# 12v-switch.net
KiCad netlist of a schematic drawn in EAGLE
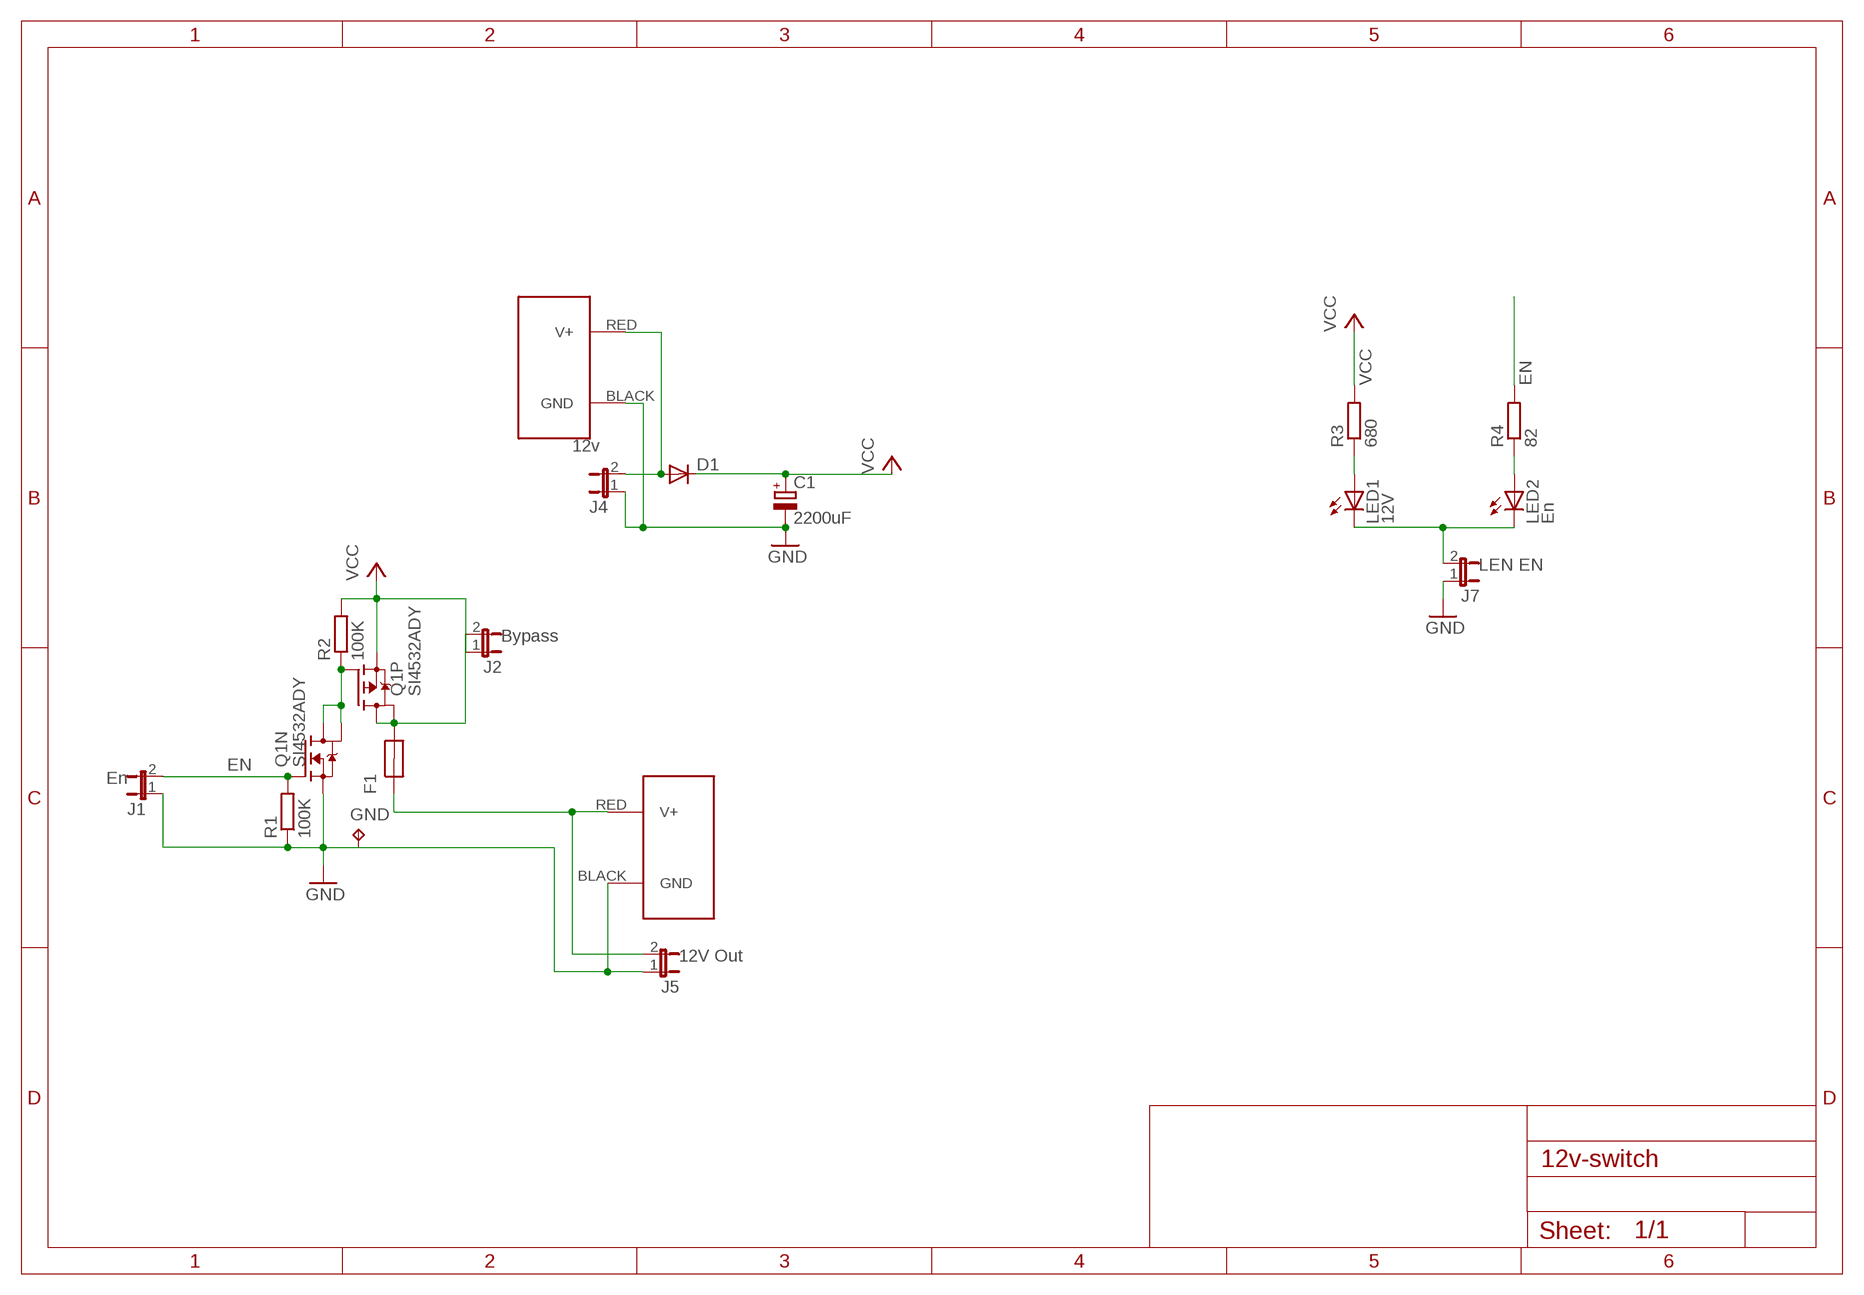
[diagram p0: schematic, sheet 1]

(export (version "E")
  (design (tool "Eeschema 10.0.6"))
  (components
    (comp (ref "C1")
      (value "2200uF")
      (footprint "eagle-import:E5-13")
      (libsource (lib "eagle-import") (part "CPOL-EUE5-13"))
    )
    (comp (ref "D1")
      (value "DIODE-SMB")
      (footprint "eagle-import:SMB")
      (libsource (lib "eagle-import") (part "DIODE-SMB"))
    )
    (comp (ref "F1")
      (value "MF-MSMF110")
      (footprint "eagle-import:1812")
      (libsource (lib "eagle-import") (part "MF-MSMF110"))
    )
    (comp (ref "GND")
      (value "5V B")
      (footprint "eagle-import:B1,27")
      (libsource (lib "eagle-import") (part "TPB1,27"))
    )
    (comp (ref "J1")
      (value "En")
      (footprint "eagle-import:2-MOLEX")
      (libsource (lib "eagle-import") (part "2-PIN-MOLEX"))
    )
    (comp (ref "J2")
      (value "Bypass")
      (footprint "eagle-import:2-MOLEX")
      (libsource (lib "eagle-import") (part "2-PIN-MOLEX"))
    )
    (comp (ref "J3")
      (value "POWERPOLE_POWER25A")
      (footprint "eagle-import:POWERPOLE_PAIR_25A")
      (libsource (lib "eagle-import") (part "POWERPOLE_POWER25A"))
    )
    (comp (ref "J4")
      (value "12v")
      (footprint "eagle-import:2-MOLEX")
      (libsource (lib "eagle-import") (part "2-PIN-MOLEX"))
    )
    (comp (ref "J5")
      (value "12V Out")
      (footprint "eagle-import:2-MOLEX")
      (libsource (lib "eagle-import") (part "2-PIN-MOLEX"))
    )
    (comp (ref "J6")
      (value "POWERPOLE_POWER25A")
      (footprint "eagle-import:POWERPOLE_PAIR_25A")
      (libsource (lib "eagle-import") (part "POWERPOLE_POWER25A"))
    )
    (comp (ref "J7")
      (value "LEN EN")
      (footprint "eagle-import:2-MOLEX")
      (libsource (lib "eagle-import") (part "2-PIN-MOLEX"))
    )
    (comp (ref "LED1")
      (value "12V")
      (footprint "eagle-import:CHIP-LED0805")
      (libsource (lib "eagle-import") (part "LEDCHIP-LED0805"))
    )
    (comp (ref "LED2")
      (value "En")
      (footprint "eagle-import:CHIP-LED0805")
      (libsource (lib "eagle-import") (part "LEDCHIP-LED0805"))
    )
    (comp (ref "Q1")
      (value "SI4532ADY")
      (footprint "eagle-import:SO8")
      (libsource (lib "eagle-import") (part "SI4532ADY"))
    )
    (comp (ref "R1")
      (value "100K")
      (footprint "eagle-import:R0805")
      (libsource (lib "eagle-import") (part "R-EU_R0805"))
    )
    (comp (ref "R2")
      (value "100K")
      (footprint "eagle-import:R0805")
      (libsource (lib "eagle-import") (part "R-EU_R0805"))
    )
    (comp (ref "R3")
      (value "680")
      (footprint "eagle-import:R0805")
      (libsource (lib "eagle-import") (part "R-EU_R0805"))
    )
    (comp (ref "R4")
      (value "82")
      (footprint "eagle-import:R0805")
      (libsource (lib "eagle-import") (part "R-EU_R0805"))
    )
  )
  (nets
    (net (code "1") (name "/EN") (class "Default")
      (node (ref "J1") (pin "2") (pinfunction "2_2") (pintype "passive"))
      (node (ref "Q1") (pin "2") (pinfunction "G_2") (pintype "passive"))
      (node (ref "R1") (pin "2") (pinfunction "2_2") (pintype "passive"))
      (node (ref "R4") (pin "2") (pinfunction "2_2") (pintype "passive"))
    )
    (net (code "2") (name "GND") (class "Default")
      (node (ref "C1") (pin "-") (pinfunction "-_-") (pintype "passive"))
      (node (ref "GND") (pin "TP") (pinfunction "TP_TP") (pintype "input"))
      (node (ref "J1") (pin "1") (pinfunction "1_1") (pintype "passive"))
      (node (ref "J3") (pin "BLACK") (pinfunction "GND_BLACK") (pintype "power_in"))
      (node (ref "J4") (pin "1") (pinfunction "1_1") (pintype "passive"))
      (node (ref "J5") (pin "1") (pinfunction "1_1") (pintype "passive"))
      (node (ref "J6") (pin "BLACK") (pinfunction "GND_BLACK") (pintype "power_in"))
      (node (ref "J7") (pin "1") (pinfunction "1_1") (pintype "passive"))
      (node (ref "Q1") (pin "1") (pinfunction "S_1") (pintype "passive"))
      (node (ref "R1") (pin "1") (pinfunction "1_1") (pintype "passive"))
    )
    (net (code "3") (name "Net-(F1-P$1)") (class "Default")
      (node (ref "F1") (pin "1") (pinfunction "P$1_1") (pintype "bidirectional"))
      (node (ref "J5") (pin "2") (pinfunction "2_2") (pintype "passive"))
      (node (ref "J6") (pin "RED") (pinfunction "V+_RED") (pintype "power_in"))
    )
    (net (code "4") (name "Net-(F1-P$2)") (class "Default")
      (node (ref "F1") (pin "2") (pinfunction "P$2_2") (pintype "bidirectional"))
      (node (ref "J2") (pin "2") (pinfunction "2_2") (pintype "passive"))
      (node (ref "Q1") (pin "5") (pinfunction "D_5") (pintype "passive"))
      (node (ref "Q1") (pin "6") (pinfunction "D_6") (pintype "passive"))
    )
    (net (code "5") (name "Net-(J3-V+)") (class "Default")
      (node (ref "D1") (pin "A") (pinfunction "A_A") (pintype "passive"))
      (node (ref "J3") (pin "RED") (pinfunction "V+_RED") (pintype "power_in"))
      (node (ref "J4") (pin "2") (pinfunction "2_2") (pintype "passive"))
    )
    (net (code "6") (name "Net-(J7-Pad2)") (class "Default")
      (node (ref "J7") (pin "2") (pinfunction "2_2") (pintype "passive"))
      (node (ref "LED1") (pin "C") (pinfunction "C_C") (pintype "passive"))
      (node (ref "LED2") (pin "C") (pinfunction "C_C") (pintype "passive"))
    )
    (net (code "7") (name "Net-(LED1-PadA)") (class "Default")
      (node (ref "LED1") (pin "A") (pinfunction "A_A") (pintype "passive"))
      (node (ref "R3") (pin "1") (pinfunction "1_1") (pintype "passive"))
    )
    (net (code "8") (name "Net-(LED2-PadA)") (class "Default")
      (node (ref "LED2") (pin "A") (pinfunction "A_A") (pintype "passive"))
      (node (ref "R4") (pin "1") (pinfunction "1_1") (pintype "passive"))
    )
    (net (code "9") (name "Net-(Q1B-G)") (class "Default")
      (node (ref "Q1") (pin "4") (pinfunction "G_4") (pintype "passive"))
      (node (ref "Q1") (pin "7") (pinfunction "D_7") (pintype "passive"))
      (node (ref "Q1") (pin "8") (pinfunction "D_8") (pintype "passive"))
      (node (ref "R2") (pin "1") (pinfunction "1_1") (pintype "passive"))
    )
    (net (code "10") (name "VCC") (class "Default")
      (node (ref "C1") (pin "+") (pinfunction "+_+") (pintype "passive"))
      (node (ref "D1") (pin "C") (pinfunction "C_C") (pintype "passive"))
      (node (ref "J2") (pin "1") (pinfunction "1_1") (pintype "passive"))
      (node (ref "Q1") (pin "3") (pinfunction "S_3") (pintype "passive"))
      (node (ref "R2") (pin "2") (pinfunction "2_2") (pintype "passive"))
      (node (ref "R3") (pin "2") (pinfunction "2_2") (pintype "passive"))
    )
  )
)
